# CONNECTORS2.net
KiCad netlist of a schematic drawn in Altium Designer
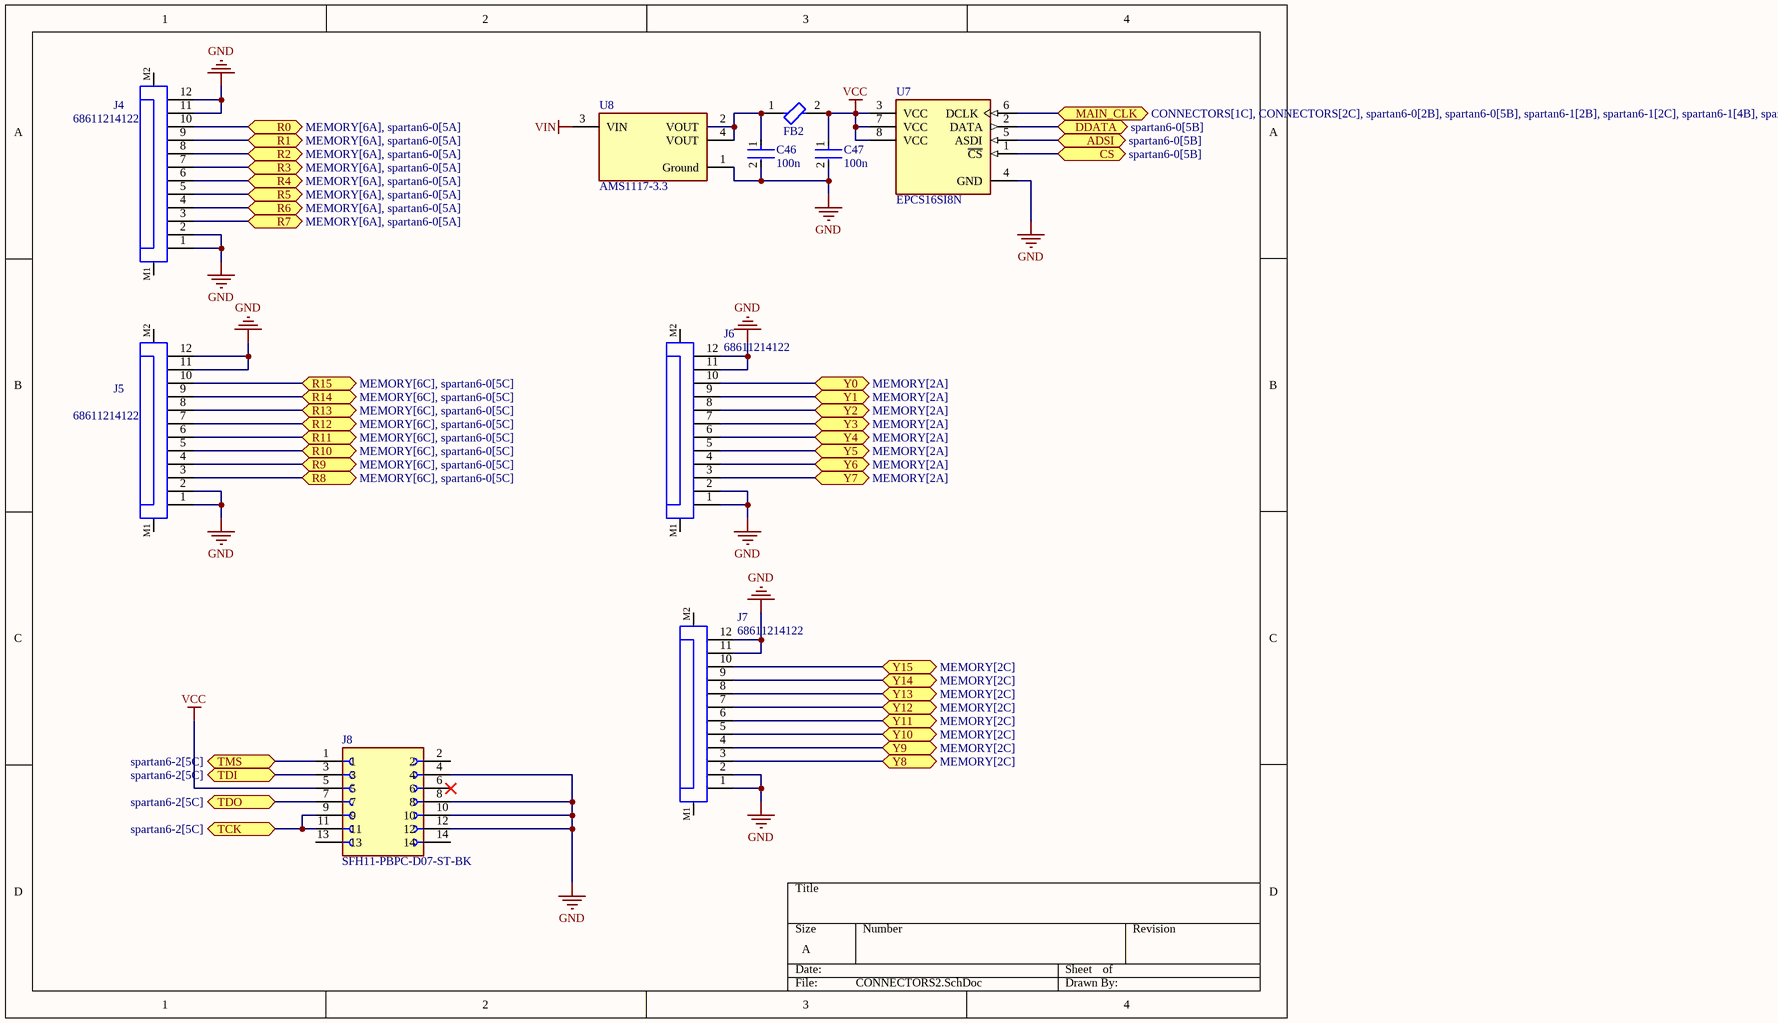
[diagram p0: CONNECTORS2.SchDoc]

(export (version "E")
  (design (tool "Eeschema 10.0.6"))
  (components
    (comp (ref "C46")
      (value "100n")
      (footprint "FP-CL10-IPC_C")
      (description "Cap Ceramic 4.7uF 10V X5R ±10% Pad SMD 0603 +85°C T/R")
      (fields (field (name "TOLERANCE") "10%"))
      (libsource (lib "Altium Content Vault") (part "b4654b650e69147ec39a6b967a45e02"))
    )
    (comp (ref "C47")
      (value "100n")
      (footprint "FP-CL10-IPC_C")
      (description "Cap Ceramic 4.7uF 10V X5R ±10% Pad SMD 0603 +85°C T/R")
      (fields (field (name "TOLERANCE") "10%"))
      (libsource (lib "Altium Content Vault") (part "b4654b650e69147ec39a6b967a45e02"))
    )
    (comp (ref "FB2")
      (value "BLM18KG121TN1D")
      (footprint "FP-BLM18-0_15-t0_6-d1_2-IPC_A")
      (description "FERRITE BEAD 120 OHM 0603 1LN")
      (fields (field (name "TOLERANCE") "25%"))
      (libsource (lib "Altium Content Vault") (part "5f30dd21d616792df468990f7003faa"))
    )
    (comp (ref "J4")
      (value "68611214122")
      (footprint "68611214122")
      (libsource (lib "Altium Content Vault") (part "FPC - 12P - 2MP"))
    )
    (comp (ref "J5")
      (value "68611214122")
      (footprint "68611214122")
      (libsource (lib "Altium Content Vault") (part "FPC - 12P - 2MP"))
    )
    (comp (ref "J6")
      (value "68611214122")
      (footprint "68611214122")
      (libsource (lib "Altium Content Vault") (part "FPC - 12P - 2MP"))
    )
    (comp (ref "J7")
      (value "68611214122")
      (footprint "68611214122")
      (libsource (lib "Altium Content Vault") (part "FPC - 12P - 2MP"))
    )
    (comp (ref "J8")
      (value "SFH11-PBPC-D07-ST-BK")
      (footprint "SULLINS_SFH11-PBPC-D07-ST-BK")
      (description "14 Position Header Connector Through Hole")
      (fields (field (name "MF") "Sullins Connector"))
      (libsource (lib "SFH11-PBPC-D07-ST-BK") (part "SFH11-PBPC-D07-ST-BK"))
    )
    (comp (ref "U7")
      (value "EPCS16SI8N")
      (footprint "FP-SOIC-8-IPC_C")
      (description "IC CONFIG DEVICE 16MBIT 8SOIC")
      (fields (field (name "MANUFACTURER") "Intel") (field (name "OBSOLETE PART") "true"))
      (libsource (lib "Altium Content Vault") (part "a709f5f6e5dc0d217256b0b7338be1e"))
    )
    (comp (ref "U8")
      (value "AMS1117-3.3")
      (footprint "FP-AMS1117-IPC_C")
      (description "LDO Voltage Regulators 1A, 3.3V")
      (fields
        (field (name "OCTOPART") "https://octopart.com/ams1117-3.3-advanced+monolithic+systems-25899300")
        (field (name "MANUFACTURER") "Advanced Monolithic Systems")
      )
      (libsource (lib "Altium Content Vault") (part "8bdbb5f8e77002000e30dd2845d0354"))
    )
  )
  (nets
    (net (code "1") (name "/ADSI") (class "Default")
      (node (ref "U7") (pin "5") (pinfunction "ASDI_5") (pintype "input"))
    )
    (net (code "2") (name "/CS") (class "Default")
      (node (ref "U7") (pin "1") (pinfunction "~{CS}_1") (pintype "input"))
    )
    (net (code "3") (name "/DDATA") (class "Default")
      (node (ref "U7") (pin "2") (pinfunction "DATA_2") (pintype "output"))
    )
    (net (code "4") (name "/MAIN_CLK") (class "Default")
      (node (ref "U7") (pin "6") (pinfunction "DCLK_6") (pintype "input"))
    )
    (net (code "5") (name "/R0") (class "Default")
      (node (ref "J4") (pin "10") (pinfunction "10_10") (pintype "passive"))
    )
    (net (code "6") (name "/R1") (class "Default")
      (node (ref "J4") (pin "9") (pinfunction "9_9") (pintype "passive"))
    )
    (net (code "7") (name "/R2") (class "Default")
      (node (ref "J4") (pin "8") (pinfunction "8_8") (pintype "passive"))
    )
    (net (code "8") (name "/R3") (class "Default")
      (node (ref "J4") (pin "7") (pinfunction "7_7") (pintype "passive"))
    )
    (net (code "9") (name "/R4") (class "Default")
      (node (ref "J4") (pin "6") (pinfunction "6_6") (pintype "passive"))
    )
    (net (code "10") (name "/R5") (class "Default")
      (node (ref "J4") (pin "5") (pinfunction "5_5") (pintype "passive"))
    )
    (net (code "11") (name "/R6") (class "Default")
      (node (ref "J4") (pin "4") (pinfunction "4_4") (pintype "passive"))
    )
    (net (code "12") (name "/R7") (class "Default")
      (node (ref "J4") (pin "3") (pinfunction "3_3") (pintype "passive"))
    )
    (net (code "13") (name "/R8") (class "Default")
      (node (ref "J5") (pin "3") (pinfunction "3_3") (pintype "passive"))
    )
    (net (code "14") (name "/R9") (class "Default")
      (node (ref "J5") (pin "4") (pinfunction "4_4") (pintype "passive"))
    )
    (net (code "15") (name "/R10") (class "Default")
      (node (ref "J5") (pin "5") (pinfunction "5_5") (pintype "passive"))
    )
    (net (code "16") (name "/R11") (class "Default")
      (node (ref "J5") (pin "6") (pinfunction "6_6") (pintype "passive"))
    )
    (net (code "17") (name "/R12") (class "Default")
      (node (ref "J5") (pin "7") (pinfunction "7_7") (pintype "passive"))
    )
    (net (code "18") (name "/R13") (class "Default")
      (node (ref "J5") (pin "8") (pinfunction "8_8") (pintype "passive"))
    )
    (net (code "19") (name "/R14") (class "Default")
      (node (ref "J5") (pin "9") (pinfunction "9_9") (pintype "passive"))
    )
    (net (code "20") (name "/R15") (class "Default")
      (node (ref "J5") (pin "10") (pinfunction "10_10") (pintype "passive"))
    )
    (net (code "21") (name "/TCK") (class "Default")
      (node (ref "J8") (pin "11") (pinfunction "11_11") (pintype "passive"))
      (node (ref "J8") (pin "9") (pinfunction "9_9") (pintype "passive"))
    )
    (net (code "22") (name "/TDI") (class "Default")
      (node (ref "J8") (pin "3") (pinfunction "3_3") (pintype "passive"))
    )
    (net (code "23") (name "/TDO") (class "Default")
      (node (ref "J8") (pin "7") (pinfunction "7_7") (pintype "passive"))
    )
    (net (code "24") (name "/TMS") (class "Default")
      (node (ref "J8") (pin "1") (pinfunction "1_1") (pintype "passive"))
    )
    (net (code "25") (name "/Y0") (class "Default")
      (node (ref "J6") (pin "10") (pinfunction "10_10") (pintype "passive"))
    )
    (net (code "26") (name "/Y1") (class "Default")
      (node (ref "J6") (pin "9") (pinfunction "9_9") (pintype "passive"))
    )
    (net (code "27") (name "/Y2") (class "Default")
      (node (ref "J6") (pin "8") (pinfunction "8_8") (pintype "passive"))
    )
    (net (code "28") (name "/Y3") (class "Default")
      (node (ref "J6") (pin "7") (pinfunction "7_7") (pintype "passive"))
    )
    (net (code "29") (name "/Y4") (class "Default")
      (node (ref "J6") (pin "6") (pinfunction "6_6") (pintype "passive"))
    )
    (net (code "30") (name "/Y5") (class "Default")
      (node (ref "J6") (pin "5") (pinfunction "5_5") (pintype "passive"))
    )
    (net (code "31") (name "/Y6") (class "Default")
      (node (ref "J6") (pin "4") (pinfunction "4_4") (pintype "passive"))
    )
    (net (code "32") (name "/Y7") (class "Default")
      (node (ref "J6") (pin "3") (pinfunction "3_3") (pintype "passive"))
    )
    (net (code "33") (name "/Y8") (class "Default")
      (node (ref "J7") (pin "3") (pinfunction "3_3") (pintype "passive"))
    )
    (net (code "34") (name "/Y9") (class "Default")
      (node (ref "J7") (pin "4") (pinfunction "4_4") (pintype "passive"))
    )
    (net (code "35") (name "/Y10") (class "Default")
      (node (ref "J7") (pin "5") (pinfunction "5_5") (pintype "passive"))
    )
    (net (code "36") (name "/Y11") (class "Default")
      (node (ref "J7") (pin "6") (pinfunction "6_6") (pintype "passive"))
    )
    (net (code "37") (name "/Y12") (class "Default")
      (node (ref "J7") (pin "7") (pinfunction "7_7") (pintype "passive"))
    )
    (net (code "38") (name "/Y13") (class "Default")
      (node (ref "J7") (pin "8") (pinfunction "8_8") (pintype "passive"))
    )
    (net (code "39") (name "/Y14") (class "Default")
      (node (ref "J7") (pin "9") (pinfunction "9_9") (pintype "passive"))
    )
    (net (code "40") (name "/Y15") (class "Default")
      (node (ref "J7") (pin "10") (pinfunction "10_10") (pintype "passive"))
    )
    (net (code "41") (name "GND") (class "Default")
      (node (ref "C46") (pin "2") (pinfunction "2_2") (pintype "passive"))
      (node (ref "C47") (pin "2") (pinfunction "2_2") (pintype "passive"))
      (node (ref "J4") (pin "1") (pinfunction "1_1") (pintype "passive"))
      (node (ref "J4") (pin "11") (pinfunction "11_11") (pintype "passive"))
      (node (ref "J4") (pin "12") (pinfunction "12_12") (pintype "passive"))
      (node (ref "J4") (pin "2") (pinfunction "2_2") (pintype "passive"))
      (node (ref "J5") (pin "1") (pinfunction "1_1") (pintype "passive"))
      (node (ref "J5") (pin "11") (pinfunction "11_11") (pintype "passive"))
      (node (ref "J5") (pin "12") (pinfunction "12_12") (pintype "passive"))
      (node (ref "J5") (pin "2") (pinfunction "2_2") (pintype "passive"))
      (node (ref "J6") (pin "1") (pinfunction "1_1") (pintype "passive"))
      (node (ref "J6") (pin "11") (pinfunction "11_11") (pintype "passive"))
      (node (ref "J6") (pin "12") (pinfunction "12_12") (pintype "passive"))
      (node (ref "J6") (pin "2") (pinfunction "2_2") (pintype "passive"))
      (node (ref "J7") (pin "1") (pinfunction "1_1") (pintype "passive"))
      (node (ref "J7") (pin "11") (pinfunction "11_11") (pintype "passive"))
      (node (ref "J7") (pin "12") (pinfunction "12_12") (pintype "passive"))
      (node (ref "J7") (pin "2") (pinfunction "2_2") (pintype "passive"))
      (node (ref "J8") (pin "10") (pinfunction "10_10") (pintype "passive"))
      (node (ref "J8") (pin "12") (pinfunction "12_12") (pintype "passive"))
      (node (ref "J8") (pin "4") (pinfunction "4_4") (pintype "passive"))
      (node (ref "J8") (pin "8") (pinfunction "8_8") (pintype "passive"))
      (node (ref "U7") (pin "4") (pinfunction "GND_4") (pintype "power_in"))
      (node (ref "U8") (pin "1") (pinfunction "Ground_1") (pintype "power_in"))
    )
    (net (code "42") (name "Net-(C46-Pad1)") (class "Default")
      (node (ref "C46") (pin "1") (pinfunction "1_1") (pintype "passive"))
      (node (ref "FB2") (pin "1") (pinfunction "1_1") (pintype "passive"))
      (node (ref "U8") (pin "2") (pinfunction "VOUT_2") (pintype "passive"))
      (node (ref "U8") (pin "4") (pinfunction "VOUT_4") (pintype "passive"))
    )
    (net (code "43") (name "VCC") (class "Default")
      (node (ref "C47") (pin "1") (pinfunction "1_1") (pintype "passive"))
      (node (ref "FB2") (pin "2") (pinfunction "2_2") (pintype "passive"))
      (node (ref "J8") (pin "5") (pinfunction "5_5") (pintype "passive"))
      (node (ref "U7") (pin "3") (pinfunction "VCC_3") (pintype "power_in"))
      (node (ref "U7") (pin "7") (pinfunction "VCC_7") (pintype "power_in"))
      (node (ref "U7") (pin "8") (pinfunction "VCC_8") (pintype "power_in"))
    )
    (net (code "44") (name "VIN") (class "Default")
      (node (ref "U8") (pin "3") (pinfunction "VIN_3") (pintype "power_in"))
    )
    (net (code "45") (name "unconnected-(J4-PadM1)") (class "Default")
      (node (ref "J4") (pin "M1") (pinfunction "M1_M1") (pintype "passive"))
    )
    (net (code "46") (name "unconnected-(J4-PadM2)") (class "Default")
      (node (ref "J4") (pin "M2") (pinfunction "M2_M2") (pintype "passive"))
    )
    (net (code "47") (name "unconnected-(J5-PadM1)") (class "Default")
      (node (ref "J5") (pin "M1") (pinfunction "M1_M1") (pintype "passive"))
    )
    (net (code "48") (name "unconnected-(J5-PadM2)") (class "Default")
      (node (ref "J5") (pin "M2") (pinfunction "M2_M2") (pintype "passive"))
    )
    (net (code "49") (name "unconnected-(J6-PadM1)") (class "Default")
      (node (ref "J6") (pin "M1") (pinfunction "M1_M1") (pintype "passive"))
    )
    (net (code "50") (name "unconnected-(J6-PadM2)") (class "Default")
      (node (ref "J6") (pin "M2") (pinfunction "M2_M2") (pintype "passive"))
    )
    (net (code "51") (name "unconnected-(J7-PadM1)") (class "Default")
      (node (ref "J7") (pin "M1") (pinfunction "M1_M1") (pintype "passive"))
    )
    (net (code "52") (name "unconnected-(J7-PadM2)") (class "Default")
      (node (ref "J7") (pin "M2") (pinfunction "M2_M2") (pintype "passive"))
    )
    (net (code "53") (name "unconnected-(J8-Pad2)") (class "Default")
      (node (ref "J8") (pin "2") (pinfunction "2_2") (pintype "passive"))
    )
    (net (code "54") (name "unconnected-(J8-Pad6)") (class "Default")
      (node (ref "J8") (pin "6") (pinfunction "6_6") (pintype "passive+no_connect"))
    )
    (net (code "55") (name "unconnected-(J8-Pad13)") (class "Default")
      (node (ref "J8") (pin "13") (pinfunction "13_13") (pintype "passive"))
    )
    (net (code "56") (name "unconnected-(J8-Pad14)") (class "Default")
      (node (ref "J8") (pin "14") (pinfunction "14_14") (pintype "passive"))
    )
  )
)
